# upper_traced.net
KiCad netlist of a schematic drawn in EAGLE
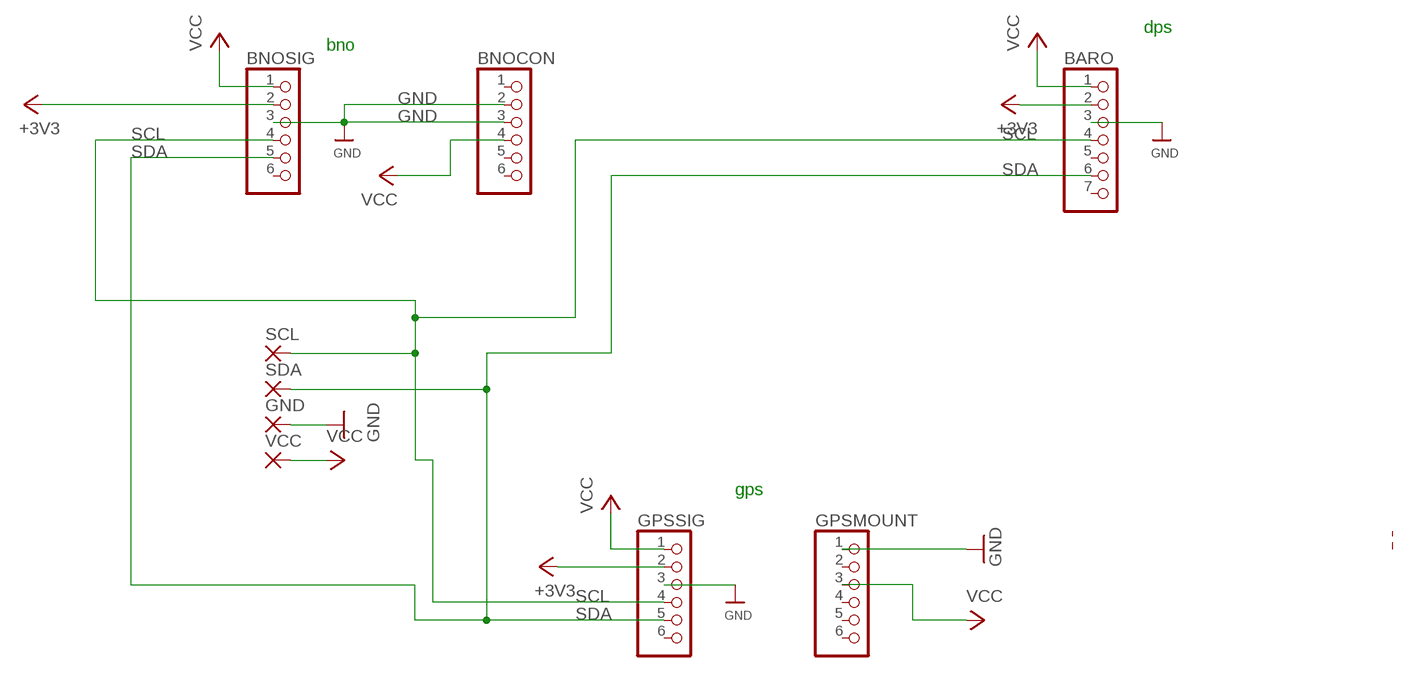
[diagram p0: schematic, sheet 1]

(export (version "E")
  (design (tool "Eeschema 10.0.6"))
  (components
    (comp (ref "BARO")
      (value "HEADER-1X770MIL")
      (footprint "eagle-import:1X07_ROUND_70")
      (libsource (lib "eagle-import") (part "HEADER-1X770MIL"))
    )
    (comp (ref "BNOCON")
      (value "HEADER-1X670MIL")
      (footprint "eagle-import:1X06_ROUND_70")
      (libsource (lib "eagle-import") (part "HEADER-1X670MIL"))
    )
    (comp (ref "BNOSIG")
      (value "HEADER-1X670MIL")
      (footprint "eagle-import:1X06_ROUND_70")
      (libsource (lib "eagle-import") (part "HEADER-1X670MIL"))
    )
    (comp (ref "GND")
      (value "3,17/1,1")
      (footprint "eagle-import:3,17_1,1")
      (libsource (lib "eagle-import") (part "3,17/1,1"))
    )
    (comp (ref "GPSMOUNT")
      (value "HEADER-1X670MIL")
      (footprint "eagle-import:1X06_ROUND_70")
      (libsource (lib "eagle-import") (part "HEADER-1X670MIL"))
    )
    (comp (ref "GPSSIG")
      (value "HEADER-1X670MIL")
      (footprint "eagle-import:1X06_ROUND_70")
      (libsource (lib "eagle-import") (part "HEADER-1X670MIL"))
    )
    (comp (ref "SCL")
      (value "3,17/1,1")
      (footprint "eagle-import:3,17_1,1")
      (libsource (lib "eagle-import") (part "3,17/1,1"))
    )
    (comp (ref "SDA")
      (value "3,17/1,1")
      (footprint "eagle-import:3,17_1,1")
      (libsource (lib "eagle-import") (part "3,17/1,1"))
    )
    (comp (ref "VCC")
      (value "3,17/1,1")
      (footprint "eagle-import:3,17_1,1")
      (libsource (lib "eagle-import") (part "3,17/1,1"))
    )
  )
  (nets
    (net (code "1") (name "+3V3") (class "Default")
      (node (ref "BARO") (pin "2") (pinfunction "2_2") (pintype "passive"))
      (node (ref "BNOSIG") (pin "2") (pinfunction "2_2") (pintype "passive"))
      (node (ref "GPSSIG") (pin "2") (pinfunction "2_2") (pintype "passive"))
    )
    (net (code "2") (name "/SCL") (class "Default")
      (node (ref "BARO") (pin "4") (pinfunction "4_4") (pintype "passive"))
      (node (ref "BNOSIG") (pin "4") (pinfunction "4_4") (pintype "passive"))
      (node (ref "GPSSIG") (pin "4") (pinfunction "4_4") (pintype "passive"))
      (node (ref "SCL") (pin "1") (pinfunction "P_1") (pintype "passive"))
    )
    (net (code "3") (name "/SDA") (class "Default")
      (node (ref "BARO") (pin "6") (pinfunction "6_6") (pintype "passive"))
      (node (ref "BNOSIG") (pin "5") (pinfunction "5_5") (pintype "passive"))
      (node (ref "GPSSIG") (pin "5") (pinfunction "5_5") (pintype "passive"))
      (node (ref "SDA") (pin "1") (pinfunction "P_1") (pintype "passive"))
    )
    (net (code "4") (name "GND") (class "Default")
      (node (ref "BARO") (pin "3") (pinfunction "3_3") (pintype "passive"))
      (node (ref "BNOCON") (pin "2") (pinfunction "2_2") (pintype "passive"))
      (node (ref "BNOCON") (pin "3") (pinfunction "3_3") (pintype "passive"))
      (node (ref "BNOSIG") (pin "3") (pinfunction "3_3") (pintype "passive"))
      (node (ref "GND") (pin "1") (pinfunction "P_1") (pintype "passive"))
      (node (ref "GPSMOUNT") (pin "1") (pinfunction "1_1") (pintype "passive"))
      (node (ref "GPSSIG") (pin "3") (pinfunction "3_3") (pintype "passive"))
    )
    (net (code "5") (name "VCC") (class "Default")
      (node (ref "BARO") (pin "1") (pinfunction "1_1") (pintype "passive"))
      (node (ref "BNOCON") (pin "4") (pinfunction "4_4") (pintype "passive"))
      (node (ref "BNOSIG") (pin "1") (pinfunction "1_1") (pintype "passive"))
      (node (ref "GPSMOUNT") (pin "3") (pinfunction "3_3") (pintype "passive"))
      (node (ref "GPSSIG") (pin "1") (pinfunction "1_1") (pintype "passive"))
      (node (ref "VCC") (pin "1") (pinfunction "P_1") (pintype "passive"))
    )
    (net (code "6") (name "unconnected-(BARO-Pad5)") (class "Default")
      (node (ref "BARO") (pin "5") (pinfunction "5_5") (pintype "passive"))
    )
    (net (code "7") (name "unconnected-(BARO-Pad7)") (class "Default")
      (node (ref "BARO") (pin "7") (pinfunction "7_7") (pintype "passive"))
    )
    (net (code "8") (name "unconnected-(BNOCON-Pad1)") (class "Default")
      (node (ref "BNOCON") (pin "1") (pinfunction "1_1") (pintype "passive"))
    )
    (net (code "9") (name "unconnected-(BNOCON-Pad5)") (class "Default")
      (node (ref "BNOCON") (pin "5") (pinfunction "5_5") (pintype "passive"))
    )
    (net (code "10") (name "unconnected-(BNOCON-Pad6)") (class "Default")
      (node (ref "BNOCON") (pin "6") (pinfunction "6_6") (pintype "passive"))
    )
    (net (code "11") (name "unconnected-(BNOSIG-Pad6)") (class "Default")
      (node (ref "BNOSIG") (pin "6") (pinfunction "6_6") (pintype "passive"))
    )
    (net (code "12") (name "unconnected-(GPSMOUNT-Pad2)") (class "Default")
      (node (ref "GPSMOUNT") (pin "2") (pinfunction "2_2") (pintype "passive"))
    )
    (net (code "13") (name "unconnected-(GPSMOUNT-Pad4)") (class "Default")
      (node (ref "GPSMOUNT") (pin "4") (pinfunction "4_4") (pintype "passive"))
    )
    (net (code "14") (name "unconnected-(GPSMOUNT-Pad5)") (class "Default")
      (node (ref "GPSMOUNT") (pin "5") (pinfunction "5_5") (pintype "passive"))
    )
    (net (code "15") (name "unconnected-(GPSMOUNT-Pad6)") (class "Default")
      (node (ref "GPSMOUNT") (pin "6") (pinfunction "6_6") (pintype "passive"))
    )
    (net (code "16") (name "unconnected-(GPSSIG-Pad6)") (class "Default")
      (node (ref "GPSSIG") (pin "6") (pinfunction "6_6") (pintype "passive"))
    )
  )
)
